# SNESRemote.net
KiCad netlist of a schematic drawn in EAGLE
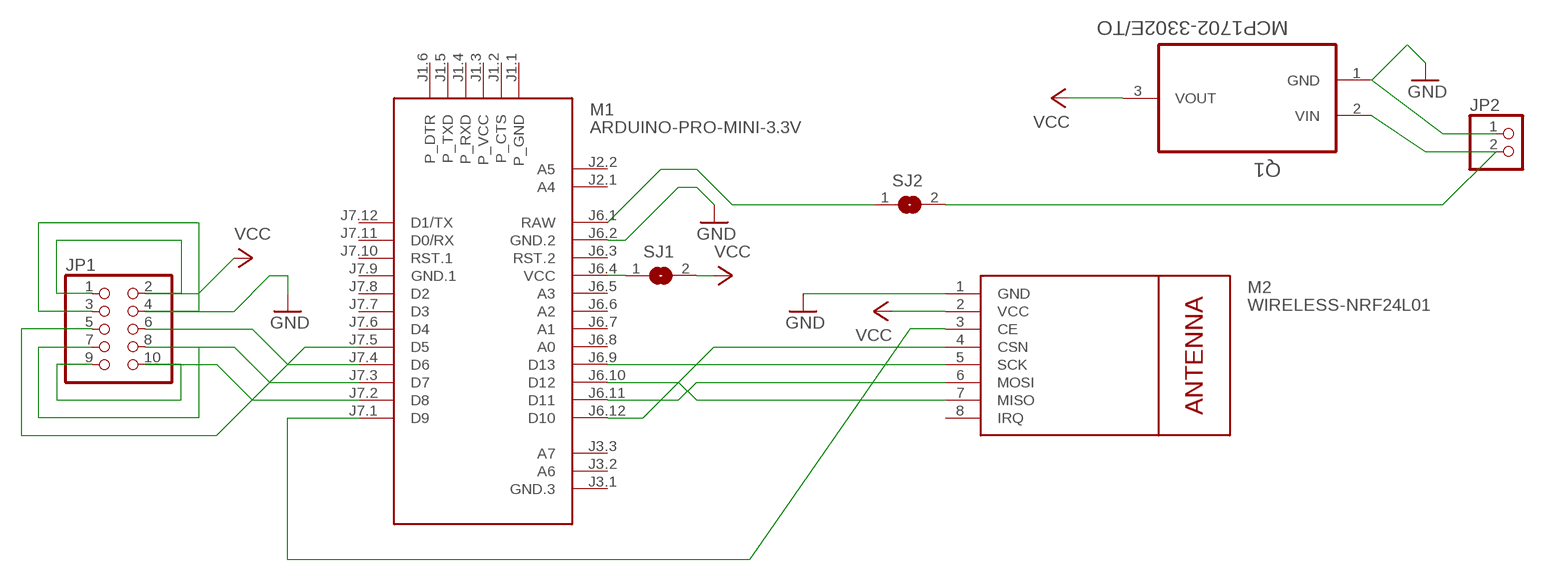
[diagram p0: schematic, sheet 1]

(export (version "E")
  (design (tool "Eeschema 10.0.6"))
  (components
    (comp (ref "JP1")
      (value "PINHD-2X5")
      (footprint "eagle-import:2X05")
      (libsource (lib "eagle-import") (part "PINHD-2X5"))
    )
    (comp (ref "JP2")
      (value "PINHD-1X2")
      (footprint "eagle-import:1X02")
      (libsource (lib "eagle-import") (part "PINHD-1X2"))
    )
    (comp (ref "M1")
      (value "ARDUINO-PRO-MINI-3.3V")
      (footprint "eagle-import:ARDUINO-PRO-MINI")
      (libsource (lib "eagle-import") (part "ARDUINO-PRO-MINI-3.3V"))
    )
    (comp (ref "M2")
      (value "WIRELESS-NRF24L01")
      (footprint "eagle-import:WIRELESS-NRF24L01")
      (libsource (lib "eagle-import") (part "WIRELESS-NRF24L01"))
    )
    (comp (ref "Q1")
      (value "MCP1702-3302E/TO")
      (footprint "eagle-import:TO127P254X533-3")
      (libsource (lib "eagle-import") (part "MCP1702-3302E/TO"))
    )
    (comp (ref "SJ1") (value "SJ") (footprint "eagle-import:SJ") (libsource (lib "eagle-import") (part "SJ")))
    (comp (ref "SJ2") (value "SJ") (footprint "eagle-import:SJ") (libsource (lib "eagle-import") (part "SJ")))
  )
  (nets
    (net (code "1") (name "/GND.1") (class "Default")
      (node (ref "M1") (pin "J7.9") (pinfunction "GND.1_J7.9") (pintype "power_in"))
    )
    (net (code "2") (name "GND") (class "Default")
      (node (ref "JP1") (pin "3") (pinfunction "3_3") (pintype "passive"))
      (node (ref "JP1") (pin "4") (pinfunction "4_4") (pintype "passive"))
      (node (ref "JP2") (pin "1") (pinfunction "1_1") (pintype "passive"))
      (node (ref "M1") (pin "J6.2") (pinfunction "GND.2_J6.2") (pintype "power_in"))
      (node (ref "M2") (pin "1") (pinfunction "GND_1") (pintype "power_in"))
      (node (ref "Q1") (pin "1") (pinfunction "GND_1") (pintype "passive"))
    )
    (net (code "3") (name "Net-(M1-D5)") (class "Default")
      (node (ref "JP1") (pin "5") (pinfunction "5_5") (pintype "passive"))
      (node (ref "M1") (pin "J7.5") (pinfunction "D5_J7.5") (pintype "bidirectional"))
    )
    (net (code "4") (name "Net-(M1-D6)") (class "Default")
      (node (ref "JP1") (pin "6") (pinfunction "6_6") (pintype "passive"))
      (node (ref "M1") (pin "J7.4") (pinfunction "D6_J7.4") (pintype "bidirectional"))
    )
    (net (code "5") (name "Net-(M1-D7)") (class "Default")
      (node (ref "JP1") (pin "7") (pinfunction "7_7") (pintype "passive"))
      (node (ref "JP1") (pin "8") (pinfunction "8_8") (pintype "passive"))
      (node (ref "M1") (pin "J7.3") (pinfunction "D7_J7.3") (pintype "bidirectional"))
    )
    (net (code "6") (name "Net-(M1-D8)") (class "Default")
      (node (ref "JP1") (pin "10") (pinfunction "10_10") (pintype "passive"))
      (node (ref "JP1") (pin "9") (pinfunction "9_9") (pintype "passive"))
      (node (ref "M1") (pin "J7.2") (pinfunction "D8_J7.2") (pintype "bidirectional"))
    )
    (net (code "7") (name "Net-(M1-D9)") (class "Default")
      (node (ref "M1") (pin "J7.1") (pinfunction "D9_J7.1") (pintype "bidirectional"))
      (node (ref "M2") (pin "3") (pinfunction "CE_3") (pintype "bidirectional"))
    )
    (net (code "8") (name "Net-(M1-D10)") (class "Default")
      (node (ref "M1") (pin "J6.12") (pinfunction "D10_J6.12") (pintype "bidirectional"))
      (node (ref "M2") (pin "4") (pinfunction "CSN_4") (pintype "bidirectional"))
    )
    (net (code "9") (name "Net-(M1-D11)") (class "Default")
      (node (ref "M1") (pin "J6.11") (pinfunction "D11_J6.11") (pintype "bidirectional"))
      (node (ref "M2") (pin "6") (pinfunction "MOSI_6") (pintype "bidirectional"))
    )
    (net (code "10") (name "Net-(M1-D12)") (class "Default")
      (node (ref "M1") (pin "J6.10") (pinfunction "D12_J6.10") (pintype "bidirectional"))
      (node (ref "M2") (pin "7") (pinfunction "MISO_7") (pintype "bidirectional"))
    )
    (net (code "11") (name "Net-(M1-D13)") (class "Default")
      (node (ref "M1") (pin "J6.9") (pinfunction "D13_J6.9") (pintype "bidirectional"))
      (node (ref "M2") (pin "5") (pinfunction "SCK_5") (pintype "bidirectional"))
    )
    (net (code "12") (name "Net-(M1-RAW)") (class "Default")
      (node (ref "M1") (pin "J6.1") (pinfunction "RAW_J6.1") (pintype "power_in"))
      (node (ref "SJ2") (pin "1") (pinfunction "1_1") (pintype "passive"))
    )
    (net (code "13") (name "Net-(M1-VCC)") (class "Default")
      (node (ref "M1") (pin "J6.4") (pinfunction "VCC_J6.4") (pintype "power_in"))
      (node (ref "SJ1") (pin "1") (pinfunction "1_1") (pintype "passive"))
    )
    (net (code "14") (name "Net-(Q1-VIN)") (class "Default")
      (node (ref "JP2") (pin "2") (pinfunction "2_2") (pintype "passive"))
      (node (ref "Q1") (pin "2") (pinfunction "VIN_2") (pintype "input"))
      (node (ref "SJ2") (pin "2") (pinfunction "2_2") (pintype "passive"))
    )
    (net (code "15") (name "VCC") (class "Default")
      (node (ref "JP1") (pin "1") (pinfunction "1_1") (pintype "passive"))
      (node (ref "JP1") (pin "2") (pinfunction "2_2") (pintype "passive"))
      (node (ref "M2") (pin "2") (pinfunction "VCC_2") (pintype "power_in"))
      (node (ref "Q1") (pin "3") (pinfunction "VOUT_3") (pintype "output"))
      (node (ref "SJ1") (pin "2") (pinfunction "2_2") (pintype "passive"))
    )
    (net (code "16") (name "unconnected-(M1-A0-PadJ6.8)") (class "Default")
      (node (ref "M1") (pin "J6.8") (pinfunction "A0_J6.8") (pintype "bidirectional"))
    )
    (net (code "17") (name "unconnected-(M1-A1-PadJ6.7)") (class "Default")
      (node (ref "M1") (pin "J6.7") (pinfunction "A1_J6.7") (pintype "bidirectional"))
    )
    (net (code "18") (name "unconnected-(M1-A2-PadJ6.6)") (class "Default")
      (node (ref "M1") (pin "J6.6") (pinfunction "A2_J6.6") (pintype "bidirectional"))
    )
    (net (code "19") (name "unconnected-(M1-A3-PadJ6.5)") (class "Default")
      (node (ref "M1") (pin "J6.5") (pinfunction "A3_J6.5") (pintype "bidirectional"))
    )
    (net (code "20") (name "unconnected-(M1-A4-PadJ2.1)") (class "Default")
      (node (ref "M1") (pin "J2.1") (pinfunction "A4_J2.1") (pintype "bidirectional"))
    )
    (net (code "21") (name "unconnected-(M1-A5-PadJ2.2)") (class "Default")
      (node (ref "M1") (pin "J2.2") (pinfunction "A5_J2.2") (pintype "bidirectional"))
    )
    (net (code "22") (name "unconnected-(M1-A6-PadJ3.2)") (class "Default")
      (node (ref "M1") (pin "J3.2") (pinfunction "A6_J3.2") (pintype "bidirectional"))
    )
    (net (code "23") (name "unconnected-(M1-A7-PadJ3.3)") (class "Default")
      (node (ref "M1") (pin "J3.3") (pinfunction "A7_J3.3") (pintype "bidirectional"))
    )
    (net (code "24") (name "unconnected-(M1-D0{slash}RX-PadJ7.11)") (class "Default")
      (node (ref "M1") (pin "J7.11") (pinfunction "D0/RX_J7.11") (pintype "bidirectional"))
    )
    (net (code "25") (name "unconnected-(M1-D1{slash}TX-PadJ7.12)") (class "Default")
      (node (ref "M1") (pin "J7.12") (pinfunction "D1/TX_J7.12") (pintype "bidirectional"))
    )
    (net (code "26") (name "unconnected-(M1-D2-PadJ7.8)") (class "Default")
      (node (ref "M1") (pin "J7.8") (pinfunction "D2_J7.8") (pintype "bidirectional"))
    )
    (net (code "27") (name "unconnected-(M1-D3-PadJ7.7)") (class "Default")
      (node (ref "M1") (pin "J7.7") (pinfunction "D3_J7.7") (pintype "bidirectional"))
    )
    (net (code "28") (name "unconnected-(M1-D4-PadJ7.6)") (class "Default")
      (node (ref "M1") (pin "J7.6") (pinfunction "D4_J7.6") (pintype "bidirectional"))
    )
    (net (code "29") (name "unconnected-(M1-GND.3-PadJ3.1)") (class "Default")
      (node (ref "M1") (pin "J3.1") (pinfunction "GND.3_J3.1") (pintype "bidirectional"))
    )
    (net (code "30") (name "unconnected-(M1-P_CTS-PadJ1.2)") (class "Default")
      (node (ref "M1") (pin "J1.2") (pinfunction "P_CTS_J1.2") (pintype "bidirectional"))
    )
    (net (code "31") (name "unconnected-(M1-P_DTR-PadJ1.6)") (class "Default")
      (node (ref "M1") (pin "J1.6") (pinfunction "P_DTR_J1.6") (pintype "bidirectional"))
    )
    (net (code "32") (name "unconnected-(M1-P_GND-PadJ1.1)") (class "Default")
      (node (ref "M1") (pin "J1.1") (pinfunction "P_GND_J1.1") (pintype "bidirectional"))
    )
    (net (code "33") (name "unconnected-(M1-P_RXD-PadJ1.4)") (class "Default")
      (node (ref "M1") (pin "J1.4") (pinfunction "P_RXD_J1.4") (pintype "bidirectional"))
    )
    (net (code "34") (name "unconnected-(M1-P_TXD-PadJ1.5)") (class "Default")
      (node (ref "M1") (pin "J1.5") (pinfunction "P_TXD_J1.5") (pintype "bidirectional"))
    )
    (net (code "35") (name "unconnected-(M1-P_VCC-PadJ1.3)") (class "Default")
      (node (ref "M1") (pin "J1.3") (pinfunction "P_VCC_J1.3") (pintype "bidirectional"))
    )
    (net (code "36") (name "unconnected-(M1-RST.1-PadJ7.10)") (class "Default")
      (node (ref "M1") (pin "J7.10") (pinfunction "RST.1_J7.10") (pintype "bidirectional"))
    )
    (net (code "37") (name "unconnected-(M1-RST.2-PadJ6.3)") (class "Default")
      (node (ref "M1") (pin "J6.3") (pinfunction "RST.2_J6.3") (pintype "bidirectional"))
    )
    (net (code "38") (name "unconnected-(M2-IRQ-Pad8)") (class "Default")
      (node (ref "M2") (pin "8") (pinfunction "IRQ_8") (pintype "bidirectional"))
    )
  )
)
